# Painel_V1_0_2.net
KiCad netlist of a schematic drawn in EAGLE
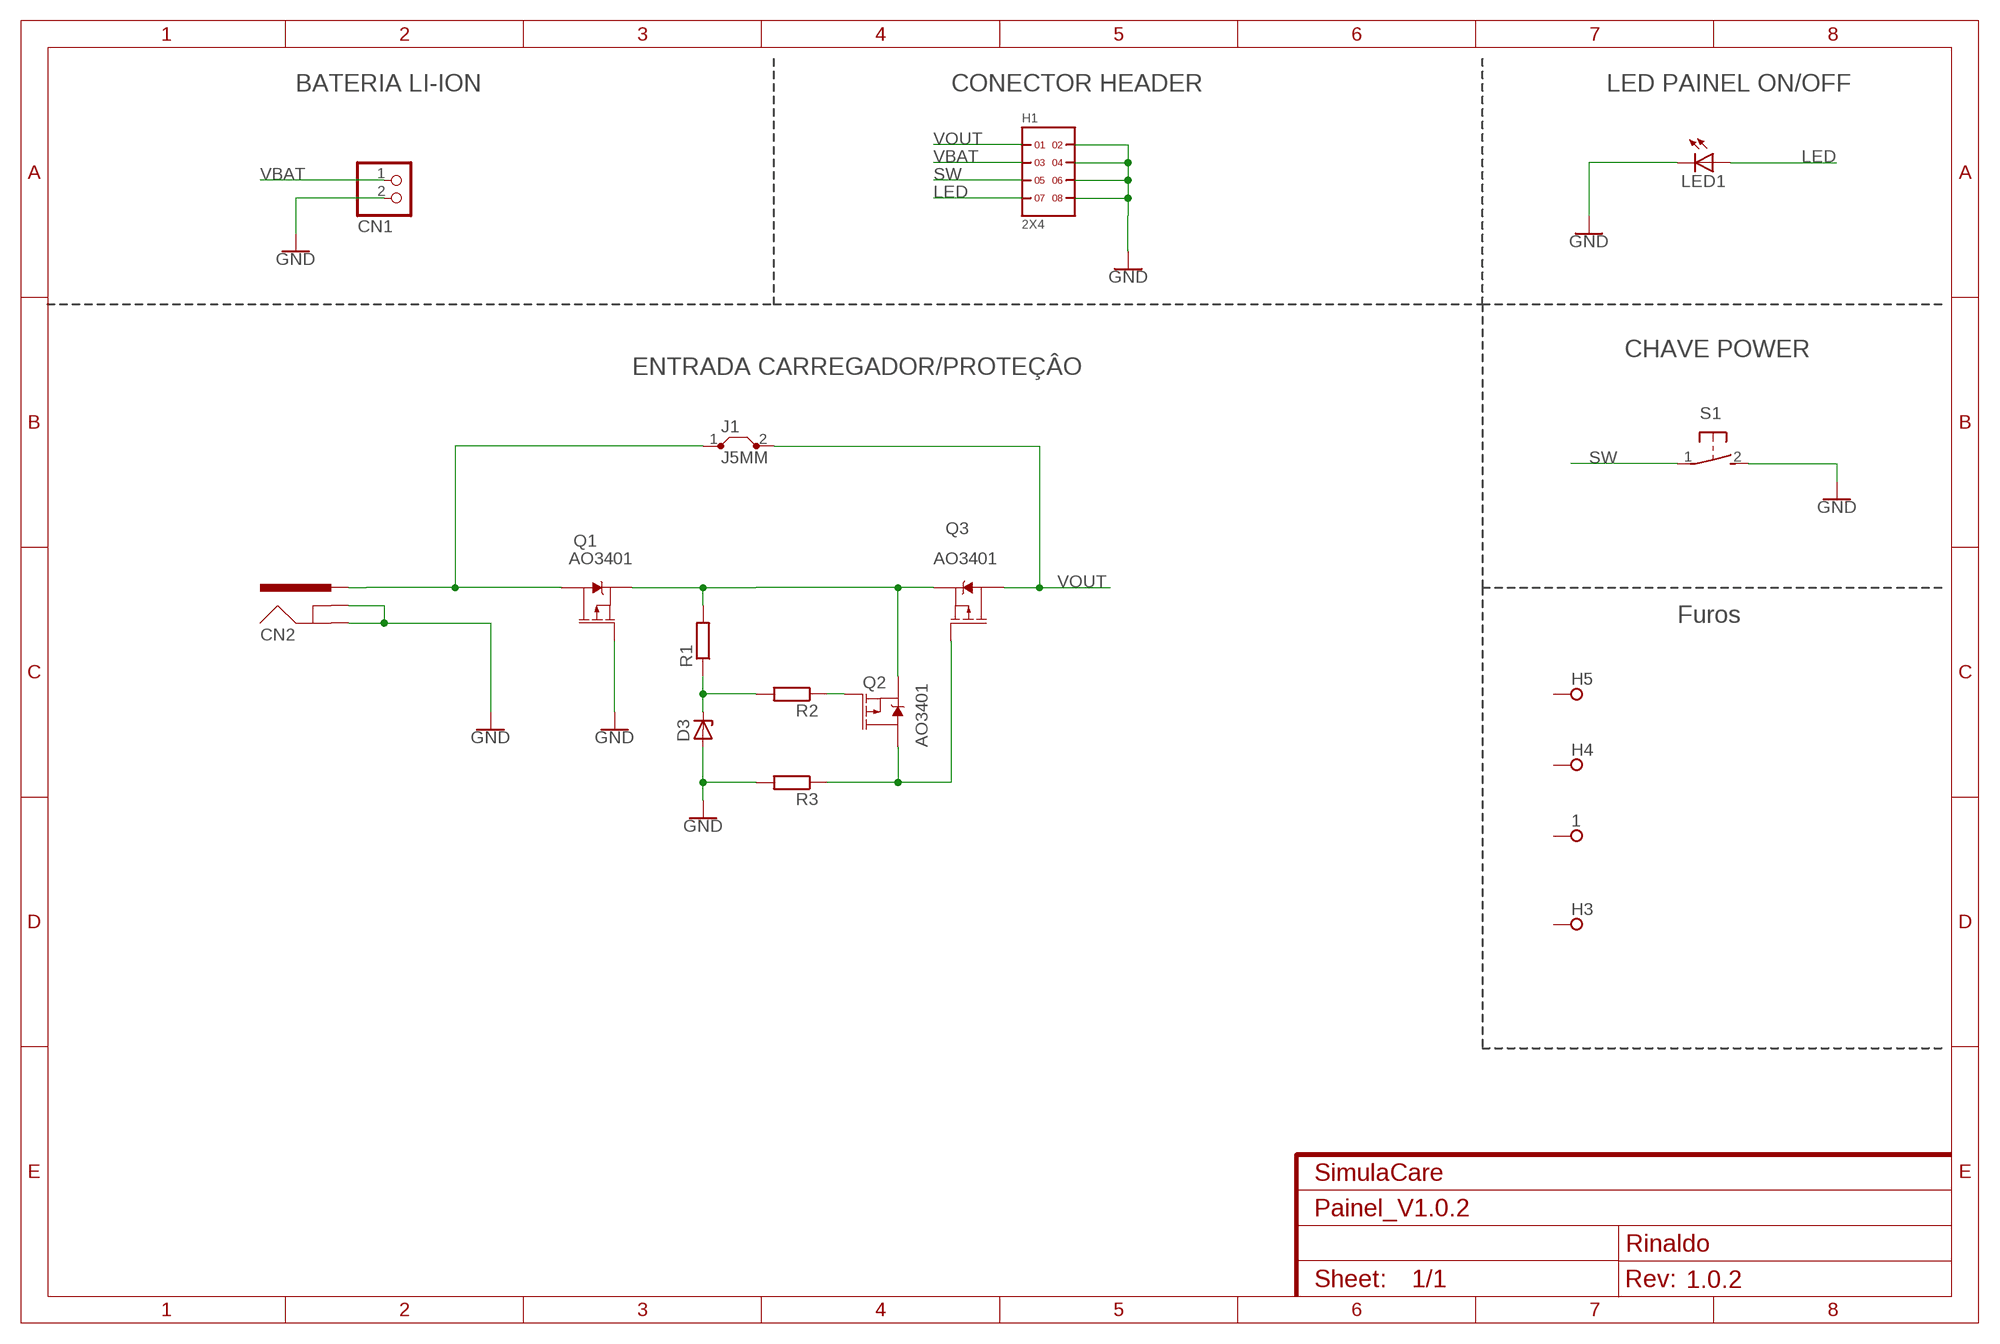
[diagram p0: schematic, sheet 1]

(export (version "E")
  (design (tool "Eeschema 10.0.6"))
  (components
    (comp (ref "1")
      (value "SPECIAL_DRILL_0.1250")
      (footprint "eagle-import:PAD_0.1250")
      (libsource (lib "eagle-import") (part "SPECIAL_DRILL_0.1250"))
    )
    (comp (ref "CN1")
      (value "JST_2PIN-THM")
      (footprint "eagle-import:JST-PH-2-THM")
      (libsource (lib "eagle-import") (part "JST_2PIN-THM"))
    )
    (comp (ref "CN2")
      (value "POWERJACK")
      (footprint "eagle-import:POWERJACK")
      (libsource (lib "eagle-import") (part "POWERJACK"))
    )
    (comp (ref "D3")
      (value "ZENER-DIODESOT23")
      (footprint "eagle-import:SOT23")
      (libsource (lib "eagle-import") (part "ZENER-DIODESOT23"))
    )
    (comp (ref "H1")
      (value "2X4")
      (footprint "eagle-import:2X4")
      (libsource (lib "eagle-import") (part "2X4"))
    )
    (comp (ref "H3")
      (value "SPECIAL_DRILL_0.1250")
      (footprint "eagle-import:PAD_0.1250")
      (libsource (lib "eagle-import") (part "SPECIAL_DRILL_0.1250"))
    )
    (comp (ref "H4")
      (value "SPECIAL_DRILL_0.1250")
      (footprint "eagle-import:PAD_0.1250")
      (libsource (lib "eagle-import") (part "SPECIAL_DRILL_0.1250"))
    )
    (comp (ref "H5")
      (value "SPECIAL_DRILL_0.1250")
      (footprint "eagle-import:PAD_0.1250")
      (libsource (lib "eagle-import") (part "SPECIAL_DRILL_0.1250"))
    )
    (comp (ref "J1")
      (value "J5MM")
      (footprint "eagle-import:05")
      (libsource (lib "eagle-import") (part "J5MM"))
    )
    (comp (ref "LED1")
      (value "LED3MM")
      (footprint "eagle-import:LED3MM")
      (libsource (lib "eagle-import") (part "LED3MM"))
    )
    (comp (ref "Q1")
      (value "AO3401")
      (footprint "eagle-import:SOT23-3")
      (libsource (lib "eagle-import") (part "MOSFET_PCH-IRLML2244"))
    )
    (comp (ref "Q2")
      (value "AO3401")
      (footprint "eagle-import:SOT23-3")
      (libsource (lib "eagle-import") (part "MOSFET_PCH-IRLML2244"))
    )
    (comp (ref "Q3")
      (value "AO3401")
      (footprint "eagle-import:SOT23-3")
      (libsource (lib "eagle-import") (part "MOSFET_PCH-IRLML2244"))
    )
    (comp (ref "R1")
      (value "R-EU_R0603")
      (footprint "eagle-import:R0603")
      (libsource (lib "eagle-import") (part "R-EU_R0603"))
    )
    (comp (ref "R2")
      (value "R-EU_R0603")
      (footprint "eagle-import:R0603")
      (libsource (lib "eagle-import") (part "R-EU_R0603"))
    )
    (comp (ref "R3")
      (value "R-EU_R0603")
      (footprint "eagle-import:R0603")
      (libsource (lib "eagle-import") (part "R-EU_R0603"))
    )
    (comp (ref "S1")
      (value "31-XX")
      (footprint "eagle-import:B3F-31XX")
      (libsource (lib "eagle-import") (part "31-XX"))
    )
  )
  (nets
    (net (code "1") (name "/LED") (class "Default")
      (node (ref "H1") (pin "7") (pinfunction "7_7") (pintype "bidirectional"))
      (node (ref "LED1") (pin "A") (pinfunction "A_A") (pintype "passive"))
    )
    (net (code "2") (name "/SW") (class "Default")
      (node (ref "H1") (pin "5") (pinfunction "5_5") (pintype "bidirectional"))
      (node (ref "S1") (pin "1") (pinfunction "P_1") (pintype "passive"))
    )
    (net (code "3") (name "/VBAT") (class "Default")
      (node (ref "CN1") (pin "1") (pinfunction "2_1") (pintype "passive"))
      (node (ref "H1") (pin "3") (pinfunction "3_3") (pintype "bidirectional"))
    )
    (net (code "4") (name "/VOUT") (class "Default")
      (node (ref "H1") (pin "1") (pinfunction "1_1") (pintype "bidirectional"))
      (node (ref "J1") (pin "2") (pinfunction "2_2") (pintype "passive"))
      (node (ref "Q3") (pin "3") (pinfunction "D_3") (pintype "bidirectional"))
    )
    (net (code "5") (name "GND") (class "Default")
      (node (ref "CN1") (pin "2") (pinfunction "1_2") (pintype "passive"))
      (node (ref "CN2") (pin "GND") (pinfunction "GND_GND") (pintype "bidirectional"))
      (node (ref "CN2") (pin "GNDBREAK") (pinfunction "GNDBREAK_GNDBREAK") (pintype "bidirectional"))
      (node (ref "D3") (pin "1") (pinfunction "A_1") (pintype "passive"))
      (node (ref "H1") (pin "2") (pinfunction "2_2") (pintype "bidirectional"))
      (node (ref "H1") (pin "4") (pinfunction "4_4") (pintype "bidirectional"))
      (node (ref "H1") (pin "6") (pinfunction "6_6") (pintype "bidirectional"))
      (node (ref "H1") (pin "8") (pinfunction "8_8") (pintype "bidirectional"))
      (node (ref "LED1") (pin "K") (pinfunction "C_K") (pintype "passive"))
      (node (ref "Q1") (pin "1") (pinfunction "G_1") (pintype "bidirectional"))
      (node (ref "R3") (pin "2") (pinfunction "2_2") (pintype "passive"))
      (node (ref "S1") (pin "2") (pinfunction "S_2") (pintype "passive"))
    )
    (net (code "6") (name "Net-(D3-C)") (class "Default")
      (node (ref "D3") (pin "3") (pinfunction "C_3") (pintype "passive"))
      (node (ref "R1") (pin "1") (pinfunction "1_1") (pintype "passive"))
      (node (ref "R2") (pin "2") (pinfunction "2_2") (pintype "passive"))
    )
    (net (code "7") (name "Net-(Q1-D)") (class "Default")
      (node (ref "CN2") (pin "PWR") (pinfunction "PWR_PWR") (pintype "bidirectional"))
      (node (ref "J1") (pin "1") (pinfunction "1_1") (pintype "passive"))
      (node (ref "Q1") (pin "3") (pinfunction "D_3") (pintype "bidirectional"))
    )
    (net (code "8") (name "Net-(Q1-S)") (class "Default")
      (node (ref "Q1") (pin "2") (pinfunction "S_2") (pintype "bidirectional"))
      (node (ref "Q2") (pin "2") (pinfunction "S_2") (pintype "bidirectional"))
      (node (ref "Q3") (pin "2") (pinfunction "S_2") (pintype "bidirectional"))
      (node (ref "R1") (pin "2") (pinfunction "2_2") (pintype "passive"))
    )
    (net (code "9") (name "Net-(Q2-D)") (class "Default")
      (node (ref "Q2") (pin "3") (pinfunction "D_3") (pintype "bidirectional"))
      (node (ref "Q3") (pin "1") (pinfunction "G_1") (pintype "bidirectional"))
      (node (ref "R3") (pin "1") (pinfunction "1_1") (pintype "passive"))
    )
    (net (code "10") (name "Net-(Q2-G)") (class "Default")
      (node (ref "Q2") (pin "1") (pinfunction "G_1") (pintype "bidirectional"))
      (node (ref "R2") (pin "1") (pinfunction "1_1") (pintype "passive"))
    )
    (net (code "11") (name "unconnected-(1-Pad1)") (class "Default")
      (node (ref "1") (pin "1") (pinfunction "1_1") (pintype "passive"))
    )
    (net (code "12") (name "unconnected-(H3-Pad1)") (class "Default")
      (node (ref "H3") (pin "1") (pinfunction "1_1") (pintype "passive"))
    )
    (net (code "13") (name "unconnected-(H4-Pad1)") (class "Default")
      (node (ref "H4") (pin "1") (pinfunction "1_1") (pintype "passive"))
    )
    (net (code "14") (name "unconnected-(H5-Pad1)") (class "Default")
      (node (ref "H5") (pin "1") (pinfunction "1_1") (pintype "passive"))
    )
  )
)
